# makey_makey.net
KiCad netlist of a schematic drawn in EAGLE
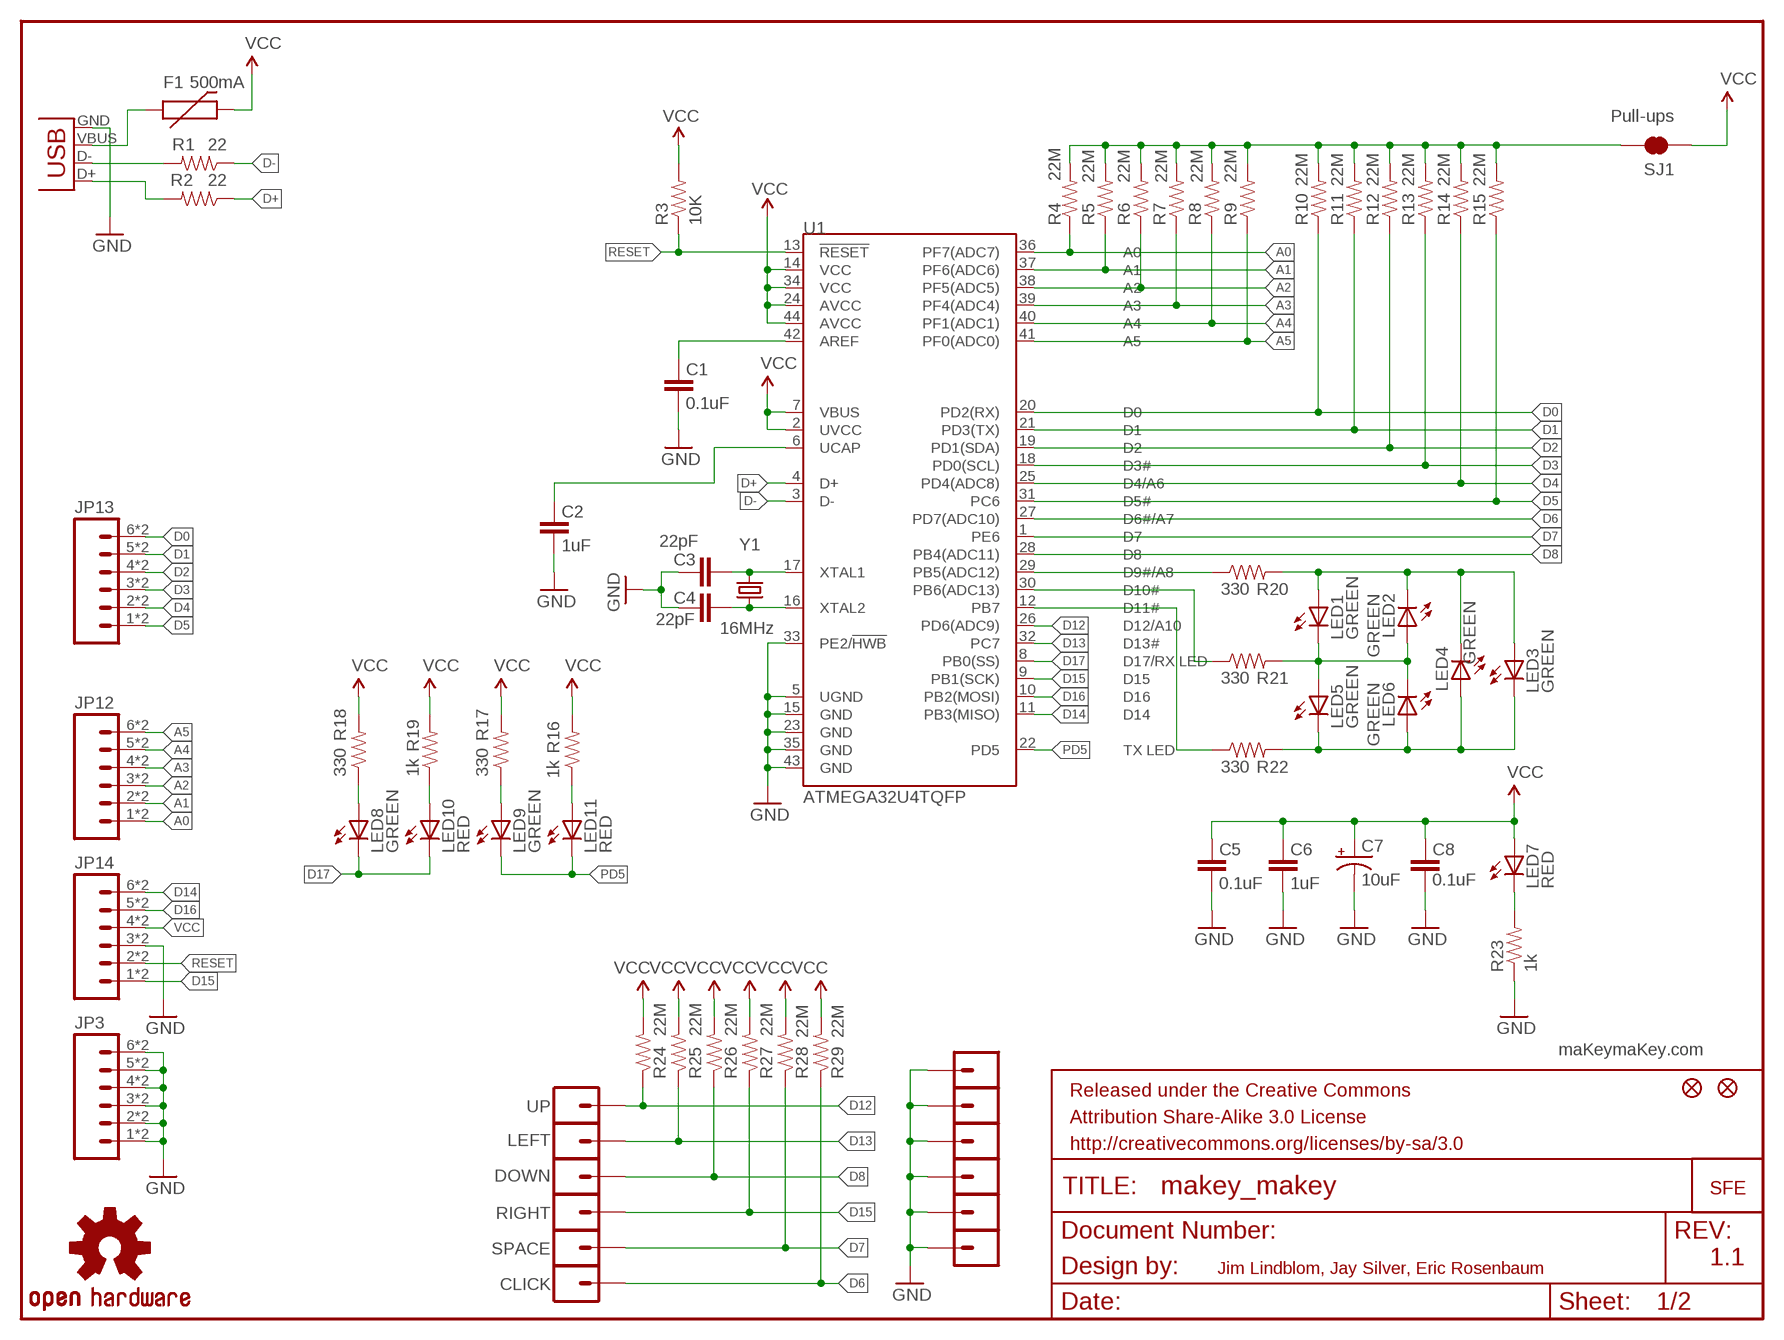
[diagram p0: schematic, sheet 1]
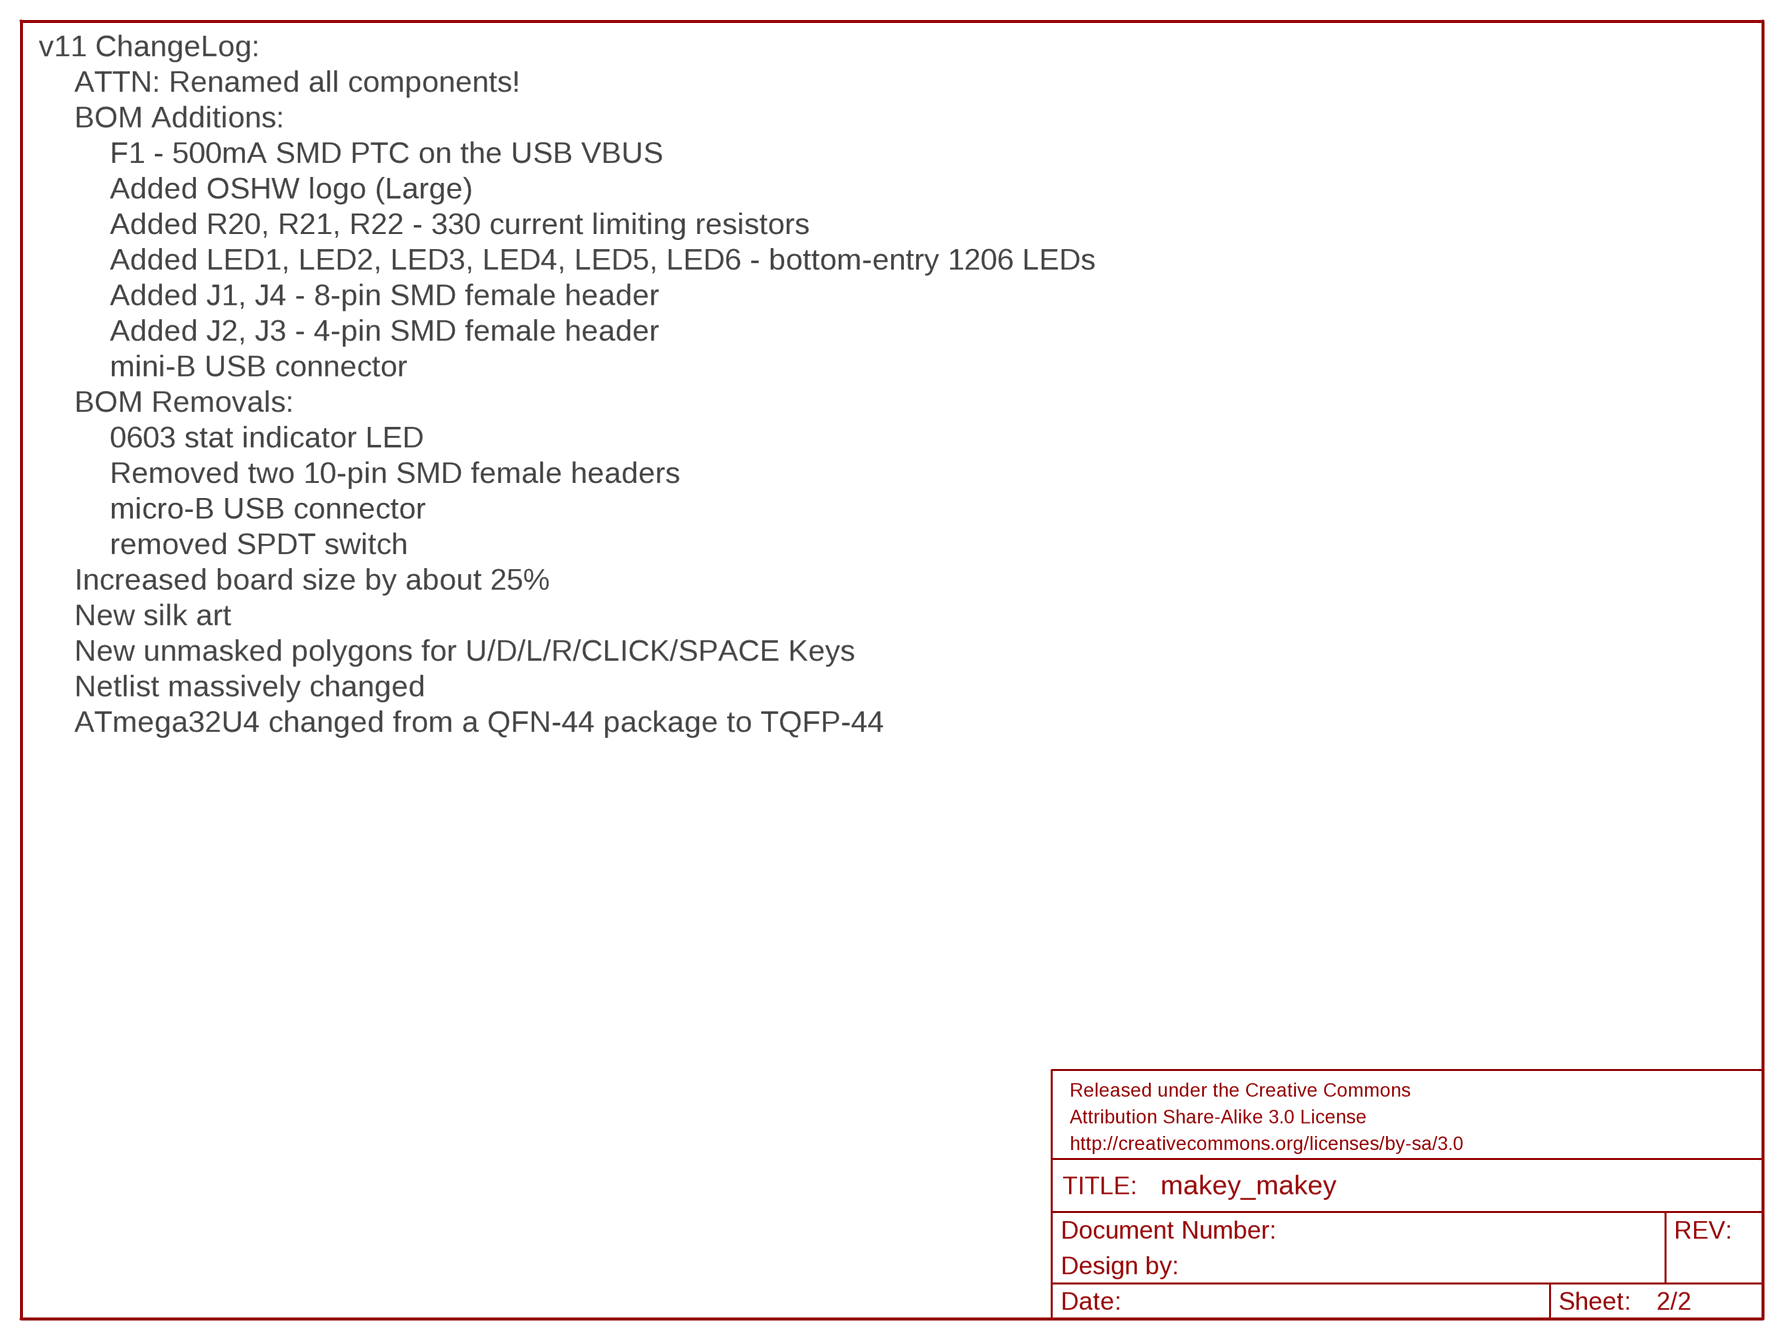
[diagram p1: schematic, sheet 2]

(export (version "E")
  (design (tool "Eeschema 10.0.6"))
  (components
    (comp (ref "C1")
      (value "0.1uF")
      (footprint "eagle-import:0402-CAP")
      (libsource (lib "eagle-import") (part "CAP0402-CAP"))
    )
    (comp (ref "C2")
      (value "1uF")
      (footprint "eagle-import:0402-CAP")
      (libsource (lib "eagle-import") (part "CAP0402-CAP"))
    )
    (comp (ref "C3")
      (value "22pF")
      (footprint "eagle-import:0402-CAP")
      (libsource (lib "eagle-import") (part "CAP0402-CAP"))
    )
    (comp (ref "C4")
      (value "22pF")
      (footprint "eagle-import:0402-CAP")
      (libsource (lib "eagle-import") (part "CAP0402-CAP"))
    )
    (comp (ref "C5")
      (value "0.1uF")
      (footprint "eagle-import:0402-CAP")
      (libsource (lib "eagle-import") (part "CAP0402-CAP"))
    )
    (comp (ref "C6")
      (value "1uF")
      (footprint "eagle-import:0402-CAP")
      (libsource (lib "eagle-import") (part "CAP0402-CAP"))
    )
    (comp (ref "C7")
      (value "10uF")
      (footprint "eagle-import:EIA3216")
      (libsource (lib "eagle-import") (part "CAP_POL1206"))
    )
    (comp (ref "C8")
      (value "0.1uF")
      (footprint "eagle-import:0402-CAP")
      (libsource (lib "eagle-import") (part "CAP0402-CAP"))
    )
    (comp (ref "CLICK")
      (value "M01ALLIGATOR-3MM")
      (footprint "eagle-import:1X01_ALLIGATOR_3MM")
      (libsource (lib "eagle-import") (part "M01ALLIGATOR-3MM"))
    )
    (comp (ref "DOWN")
      (value "M01ALLIGATOR-3MM")
      (footprint "eagle-import:1X01_ALLIGATOR_3MM")
      (libsource (lib "eagle-import") (part "M01ALLIGATOR-3MM"))
    )
    (comp (ref "F1")
      (value "500mA")
      (footprint "eagle-import:PTC-1206")
      (libsource (lib "eagle-import") (part "PTCSMD"))
    )
    (comp (ref "JP1")
      (value "FIDUCIALUFIDUCIAL")
      (footprint "eagle-import:MICRO-FIDUCIAL")
      (libsource (lib "eagle-import") (part "FIDUCIALUFIDUCIAL"))
    )
    (comp (ref "JP2")
      (value "FIDUCIALUFIDUCIAL")
      (footprint "eagle-import:MICRO-FIDUCIAL")
      (libsource (lib "eagle-import") (part "FIDUCIALUFIDUCIAL"))
    )
    (comp (ref "JP3")
      (value "M06SMD-STRAIGHT-COMBO")
      (footprint "eagle-import:1X06_SMD_STRAIGHT_COMBO")
      (libsource (lib "eagle-import") (part "M06SMD-STRAIGHT-COMBO"))
    )
    (comp (ref "JP5")
      (value "M01ALLIGATOR-3MM")
      (footprint "eagle-import:1X01_ALLIGATOR_3MM")
      (libsource (lib "eagle-import") (part "M01ALLIGATOR-3MM"))
    )
    (comp (ref "JP6")
      (value "M01ALLIGATOR-3MM")
      (footprint "eagle-import:1X01_ALLIGATOR_3MM")
      (libsource (lib "eagle-import") (part "M01ALLIGATOR-3MM"))
    )
    (comp (ref "JP7")
      (value "M01ALLIGATOR-3MM")
      (footprint "eagle-import:1X01_ALLIGATOR_3MM")
      (libsource (lib "eagle-import") (part "M01ALLIGATOR-3MM"))
    )
    (comp (ref "JP8")
      (value "M01ALLIGATOR-3MM")
      (footprint "eagle-import:1X01_ALLIGATOR_3MM")
      (libsource (lib "eagle-import") (part "M01ALLIGATOR-3MM"))
    )
    (comp (ref "JP9")
      (value "LOGO-SFENEW")
      (footprint "eagle-import:SFE-NEW-WEBLOGO")
      (libsource (lib "eagle-import") (part "LOGO-SFENEW"))
    )
    (comp (ref "JP10")
      (value "M01ALLIGATOR-3MM")
      (footprint "eagle-import:1X01_ALLIGATOR_3MM")
      (libsource (lib "eagle-import") (part "M01ALLIGATOR-3MM"))
    )
    (comp (ref "JP11")
      (value "M01ALLIGATOR-3MM")
      (footprint "eagle-import:1X01_ALLIGATOR_3MM")
      (libsource (lib "eagle-import") (part "M01ALLIGATOR-3MM"))
    )
    (comp (ref "JP12")
      (value "M06SMD-STRAIGHT-COMBO")
      (footprint "eagle-import:1X06_SMD_STRAIGHT_COMBO")
      (libsource (lib "eagle-import") (part "M06SMD-STRAIGHT-COMBO"))
    )
    (comp (ref "JP13")
      (value "M06SMD-STRAIGHT-COMBO")
      (footprint "eagle-import:1X06_SMD_STRAIGHT_COMBO")
      (libsource (lib "eagle-import") (part "M06SMD-STRAIGHT-COMBO"))
    )
    (comp (ref "JP14")
      (value "M06SMD-STRAIGHT-COMBO")
      (footprint "eagle-import:1X06_SMD_STRAIGHT_COMBO")
      (libsource (lib "eagle-import") (part "M06SMD-STRAIGHT-COMBO"))
    )
    (comp (ref "LED1")
      (value "GREEN")
      (footprint "eagle-import:LED-1206-BOTTOM")
      (libsource (lib "eagle-import") (part "LED1206-BOTTOM"))
    )
    (comp (ref "LED2")
      (value "GREEN")
      (footprint "eagle-import:LED-1206-BOTTOM")
      (libsource (lib "eagle-import") (part "LED1206-BOTTOM"))
    )
    (comp (ref "LED3")
      (value "GREEN")
      (footprint "eagle-import:LED-1206-BOTTOM")
      (libsource (lib "eagle-import") (part "LED1206-BOTTOM"))
    )
    (comp (ref "LED4")
      (value "GREEN")
      (footprint "eagle-import:LED-1206-BOTTOM")
      (libsource (lib "eagle-import") (part "LED1206-BOTTOM"))
    )
    (comp (ref "LED5")
      (value "GREEN")
      (footprint "eagle-import:LED-1206-BOTTOM")
      (libsource (lib "eagle-import") (part "LED1206-BOTTOM"))
    )
    (comp (ref "LED6")
      (value "GREEN")
      (footprint "eagle-import:LED-1206-BOTTOM")
      (libsource (lib "eagle-import") (part "LED1206-BOTTOM"))
    )
    (comp (ref "LED7")
      (value "RED")
      (footprint "eagle-import:LED-0603")
      (libsource (lib "eagle-import") (part "LED0603"))
    )
    (comp (ref "LED8")
      (value "GREEN")
      (footprint "eagle-import:LED-0603")
      (libsource (lib "eagle-import") (part "SparkFun-LED_LED0603"))
    )
    (comp (ref "LED9")
      (value "GREEN")
      (footprint "eagle-import:LED-0603")
      (libsource (lib "eagle-import") (part "SparkFun-LED_LED0603"))
    )
    (comp (ref "LED10")
      (value "RED")
      (footprint "eagle-import:LED-0603")
      (libsource (lib "eagle-import") (part "SparkFun-LED_LED0603"))
    )
    (comp (ref "LED11")
      (value "RED")
      (footprint "eagle-import:LED-0603")
      (libsource (lib "eagle-import") (part "SparkFun-LED_LED0603"))
    )
    (comp (ref "LEFT")
      (value "M01ALLIGATOR-3MM")
      (footprint "eagle-import:1X01_ALLIGATOR_3MM")
      (libsource (lib "eagle-import") (part "M01ALLIGATOR-3MM"))
    )
    (comp (ref "R1")
      (value "22")
      (footprint "eagle-import:0402-RES")
      (libsource (lib "eagle-import") (part "RESISTOR0402-RES"))
    )
    (comp (ref "R2")
      (value "22")
      (footprint "eagle-import:0402-RES")
      (libsource (lib "eagle-import") (part "RESISTOR0402-RES"))
    )
    (comp (ref "R3")
      (value "10K")
      (footprint "eagle-import:0402-RES")
      (libsource (lib "eagle-import") (part "RESISTOR0402-RES"))
    )
    (comp (ref "R4")
      (value "22M")
      (footprint "eagle-import:0402-RES")
      (libsource (lib "eagle-import") (part "RESISTOR0402-RES"))
    )
    (comp (ref "R5")
      (value "22M")
      (footprint "eagle-import:0402-RES")
      (libsource (lib "eagle-import") (part "RESISTOR0402-RES"))
    )
    (comp (ref "R6")
      (value "22M")
      (footprint "eagle-import:0402-RES")
      (libsource (lib "eagle-import") (part "RESISTOR0402-RES"))
    )
    (comp (ref "R7")
      (value "22M")
      (footprint "eagle-import:0402-RES")
      (libsource (lib "eagle-import") (part "RESISTOR0402-RES"))
    )
    (comp (ref "R8")
      (value "22M")
      (footprint "eagle-import:0402-RES")
      (libsource (lib "eagle-import") (part "RESISTOR0402-RES"))
    )
    (comp (ref "R9")
      (value "22M")
      (footprint "eagle-import:0402-RES")
      (libsource (lib "eagle-import") (part "RESISTOR0402-RES"))
    )
    (comp (ref "R10")
      (value "22M")
      (footprint "eagle-import:0402-RES")
      (libsource (lib "eagle-import") (part "RESISTOR0402-RES"))
    )
    (comp (ref "R11")
      (value "22M")
      (footprint "eagle-import:0402-RES")
      (libsource (lib "eagle-import") (part "RESISTOR0402-RES"))
    )
    (comp (ref "R12")
      (value "22M")
      (footprint "eagle-import:0402-RES")
      (libsource (lib "eagle-import") (part "RESISTOR0402-RES"))
    )
    (comp (ref "R13")
      (value "22M")
      (footprint "eagle-import:0402-RES")
      (libsource (lib "eagle-import") (part "RESISTOR0402-RES"))
    )
    (comp (ref "R14")
      (value "22M")
      (footprint "eagle-import:0402-RES")
      (libsource (lib "eagle-import") (part "RESISTOR0402-RES"))
    )
    (comp (ref "R15")
      (value "22M")
      (footprint "eagle-import:0402-RES")
      (libsource (lib "eagle-import") (part "RESISTOR0402-RES"))
    )
    (comp (ref "R16")
      (value "1k")
      (footprint "eagle-import:0402-RES")
      (libsource (lib "eagle-import") (part "SparkFun-Passives_RESISTOR0402-RES"))
    )
    (comp (ref "R17")
      (value "330")
      (footprint "eagle-import:0402-RES")
      (libsource (lib "eagle-import") (part "SparkFun-Passives_RESISTOR0402-RES"))
    )
    (comp (ref "R18")
      (value "330")
      (footprint "eagle-import:0402-RES")
      (libsource (lib "eagle-import") (part "SparkFun-Passives_RESISTOR0402-RES"))
    )
    (comp (ref "R19")
      (value "1k")
      (footprint "eagle-import:0402-RES")
      (libsource (lib "eagle-import") (part "SparkFun-Passives_RESISTOR0402-RES"))
    )
    (comp (ref "R20")
      (value "330")
      (footprint "eagle-import:0402-RES")
      (libsource (lib "eagle-import") (part "SparkFun-Passives_RESISTOR0402-RES"))
    )
    (comp (ref "R21")
      (value "330")
      (footprint "eagle-import:0402-RES")
      (libsource (lib "eagle-import") (part "SparkFun-Passives_RESISTOR0402-RES"))
    )
    (comp (ref "R22")
      (value "330")
      (footprint "eagle-import:0402-RES")
      (libsource (lib "eagle-import") (part "SparkFun-Passives_RESISTOR0402-RES"))
    )
    (comp (ref "R23")
      (value "1k")
      (footprint "eagle-import:0402-RES")
      (libsource (lib "eagle-import") (part "RESISTOR0402-RES"))
    )
    (comp (ref "R24")
      (value "22M")
      (footprint "eagle-import:0402-RES")
      (libsource (lib "eagle-import") (part "RESISTOR0402-RES"))
    )
    (comp (ref "R25")
      (value "22M")
      (footprint "eagle-import:0402-RES")
      (libsource (lib "eagle-import") (part "RESISTOR0402-RES"))
    )
    (comp (ref "R26")
      (value "22M")
      (footprint "eagle-import:0402-RES")
      (libsource (lib "eagle-import") (part "RESISTOR0402-RES"))
    )
    (comp (ref "R27")
      (value "22M")
      (footprint "eagle-import:0402-RES")
      (libsource (lib "eagle-import") (part "RESISTOR0402-RES"))
    )
    (comp (ref "R28")
      (value "22M")
      (footprint "eagle-import:0402-RES")
      (libsource (lib "eagle-import") (part "RESISTOR0402-RES"))
    )
    (comp (ref "R29")
      (value "22M")
      (footprint "eagle-import:0402-RES")
      (libsource (lib "eagle-import") (part "RESISTOR0402-RES"))
    )
    (comp (ref "RIGHT")
      (value "M01ALLIGATOR-3MM")
      (footprint "eagle-import:1X01_ALLIGATOR_3MM")
      (libsource (lib "eagle-import") (part "M01ALLIGATOR-3MM"))
    )
    (comp (ref "SJ1")
      (value "Pull-ups")
      (footprint "eagle-import:SJ_2S-TRACE")
      (libsource (lib "eagle-import") (part "SOLDERJUMPER-OLDTRACE"))
    )
    (comp (ref "SPACE")
      (value "M01ALLIGATOR-3MM")
      (footprint "eagle-import:1X01_ALLIGATOR_3MM")
      (libsource (lib "eagle-import") (part "M01ALLIGATOR-3MM"))
    )
    (comp (ref "U$1")
      (value "OSHW-LOGOM")
      (footprint "eagle-import:OSHW-LOGO-M")
      (libsource (lib "eagle-import") (part "OSHW-LOGOM"))
    )
    (comp (ref "U1")
      (value "ATMEGA32U4TQFP")
      (footprint "eagle-import:TQFP44")
      (libsource (lib "eagle-import") (part "ATMEGA32U4TQFP"))
    )
    (comp (ref "UP")
      (value "M01ALLIGATOR-3MM")
      (footprint "eagle-import:1X01_ALLIGATOR_3MM")
      (libsource (lib "eagle-import") (part "M01ALLIGATOR-3MM"))
    )
    (comp (ref "X1")
      (value "USBSMD")
      (footprint "eagle-import:USB-MINIB")
      (libsource (lib "eagle-import") (part "USBSMD"))
    )
    (comp (ref "Y1")
      (value "16MHz")
      (footprint "eagle-import:CRYSTAL-SMD-5X3")
      (libsource (lib "eagle-import") (part "CRYSTAL5X3"))
    )
  )
  (nets
    (net (code "1") (name "A0") (class "Default")
      (node (ref "JP12") (pin "1") (pinfunction "1_1") (pintype "passive"))
      (node (ref "JP12") (pin "1-2") (pinfunction "1_1-2") (pintype "passive"))
      (node (ref "R4") (pin "1") (pinfunction "1_1") (pintype "passive"))
      (node (ref "U1") (pin "36") (pinfunction "PF7(ADC7)_36") (pintype "bidirectional"))
    )
    (net (code "2") (name "A1") (class "Default")
      (node (ref "JP12") (pin "2") (pinfunction "2_2") (pintype "passive"))
      (node (ref "JP12") (pin "2-2") (pinfunction "2_2-2") (pintype "passive"))
      (node (ref "R5") (pin "1") (pinfunction "1_1") (pintype "passive"))
      (node (ref "U1") (pin "37") (pinfunction "PF6(ADC6)_37") (pintype "bidirectional"))
    )
    (net (code "3") (name "A2") (class "Default")
      (node (ref "JP12") (pin "3") (pinfunction "3_3") (pintype "passive"))
      (node (ref "JP12") (pin "3-2") (pinfunction "3_3-2") (pintype "passive"))
      (node (ref "R6") (pin "1") (pinfunction "1_1") (pintype "passive"))
      (node (ref "U1") (pin "38") (pinfunction "PF5(ADC5)_38") (pintype "bidirectional"))
    )
    (net (code "4") (name "A3") (class "Default")
      (node (ref "JP12") (pin "4") (pinfunction "4_4") (pintype "passive"))
      (node (ref "JP12") (pin "4-2") (pinfunction "4_4-2") (pintype "passive"))
      (node (ref "R7") (pin "1") (pinfunction "1_1") (pintype "passive"))
      (node (ref "U1") (pin "39") (pinfunction "PF4(ADC4)_39") (pintype "bidirectional"))
    )
    (net (code "5") (name "A4") (class "Default")
      (node (ref "JP12") (pin "5") (pinfunction "5_5") (pintype "passive"))
      (node (ref "JP12") (pin "5-2") (pinfunction "5_5-2") (pintype "passive"))
      (node (ref "R8") (pin "1") (pinfunction "1_1") (pintype "passive"))
      (node (ref "U1") (pin "40") (pinfunction "PF1(ADC1)_40") (pintype "bidirectional"))
    )
    (net (code "6") (name "A5") (class "Default")
      (node (ref "JP12") (pin "6") (pinfunction "6_6") (pintype "passive"))
      (node (ref "JP12") (pin "6-2") (pinfunction "6_6-2") (pintype "passive"))
      (node (ref "R9") (pin "1") (pinfunction "1_1") (pintype "passive"))
      (node (ref "U1") (pin "41") (pinfunction "PF0(ADC0)_41") (pintype "bidirectional"))
    )
    (net (code "7") (name "D+") (class "Default")
      (node (ref "R2") (pin "1") (pinfunction "1_1") (pintype "passive"))
      (node (ref "U1") (pin "4") (pinfunction "D+_4") (pintype "bidirectional"))
    )
    (net (code "8") (name "D-") (class "Default")
      (node (ref "R1") (pin "1") (pinfunction "1_1") (pintype "passive"))
      (node (ref "U1") (pin "3") (pinfunction "D-_3") (pintype "bidirectional"))
    )
    (net (code "9") (name "D0") (class "Default")
      (node (ref "JP13") (pin "6") (pinfunction "6_6") (pintype "passive"))
      (node (ref "JP13") (pin "6-2") (pinfunction "6_6-2") (pintype "passive"))
      (node (ref "R10") (pin "1") (pinfunction "1_1") (pintype "passive"))
      (node (ref "U1") (pin "20") (pinfunction "PD2(RX)_20") (pintype "bidirectional"))
    )
    (net (code "10") (name "D1") (class "Default")
      (node (ref "JP13") (pin "5") (pinfunction "5_5") (pintype "passive"))
      (node (ref "JP13") (pin "5-2") (pinfunction "5_5-2") (pintype "passive"))
      (node (ref "R11") (pin "1") (pinfunction "1_1") (pintype "passive"))
      (node (ref "U1") (pin "21") (pinfunction "PD3(TX)_21") (pintype "bidirectional"))
    )
    (net (code "11") (name "D2") (class "Default")
      (node (ref "JP13") (pin "4") (pinfunction "4_4") (pintype "passive"))
      (node (ref "JP13") (pin "4-2") (pinfunction "4_4-2") (pintype "passive"))
      (node (ref "R12") (pin "1") (pinfunction "1_1") (pintype "passive"))
      (node (ref "U1") (pin "19") (pinfunction "PD1(SDA)_19") (pintype "bidirectional"))
    )
    (net (code "12") (name "D3") (class "Default")
      (node (ref "JP13") (pin "3") (pinfunction "3_3") (pintype "passive"))
      (node (ref "JP13") (pin "3-2") (pinfunction "3_3-2") (pintype "passive"))
      (node (ref "R13") (pin "1") (pinfunction "1_1") (pintype "passive"))
      (node (ref "U1") (pin "18") (pinfunction "PD0(SCL)_18") (pintype "bidirectional"))
    )
    (net (code "13") (name "D4") (class "Default")
      (node (ref "JP13") (pin "2") (pinfunction "2_2") (pintype "passive"))
      (node (ref "JP13") (pin "2-2") (pinfunction "2_2-2") (pintype "passive"))
      (node (ref "R14") (pin "1") (pinfunction "1_1") (pintype "passive"))
      (node (ref "U1") (pin "25") (pinfunction "PD4(ADC8)_25") (pintype "bidirectional"))
    )
    (net (code "14") (name "D5") (class "Default")
      (node (ref "JP13") (pin "1") (pinfunction "1_1") (pintype "passive"))
      (node (ref "JP13") (pin "1-2") (pinfunction "1_1-2") (pintype "passive"))
      (node (ref "R15") (pin "1") (pinfunction "1_1") (pintype "passive"))
      (node (ref "U1") (pin "31") (pinfunction "PC6_31") (pintype "bidirectional"))
    )
    (net (code "15") (name "D6") (class "Default")
      (node (ref "CLICK") (pin "1@0") (pinfunction "1_1@0") (pintype "passive"))
      (node (ref "CLICK") (pin "1@2") (pinfunction "1_1@2") (pintype "passive"))
      (node (ref "R29") (pin "1") (pinfunction "1_1") (pintype "passive"))
      (node (ref "U1") (pin "27") (pinfunction "PD7(ADC10)_27") (pintype "bidirectional"))
    )
    (net (code "16") (name "D7") (class "Default")
      (node (ref "R28") (pin "1") (pinfunction "1_1") (pintype "passive"))
      (node (ref "SPACE") (pin "1@0") (pinfunction "1_1@0") (pintype "passive"))
      (node (ref "SPACE") (pin "1@2") (pinfunction "1_1@2") (pintype "passive"))
      (node (ref "U1") (pin "1") (pinfunction "PE6_1") (pintype "bidirectional"))
    )
    (net (code "17") (name "D8") (class "Default")
      (node (ref "DOWN") (pin "1@0") (pinfunction "1_1@0") (pintype "passive"))
      (node (ref "DOWN") (pin "1@2") (pinfunction "1_1@2") (pintype "passive"))
      (node (ref "R26") (pin "1") (pinfunction "1_1") (pintype "passive"))
      (node (ref "U1") (pin "28") (pinfunction "PB4(ADC11)_28") (pintype "bidirectional"))
    )
    (net (code "18") (name "D12") (class "Default")
      (node (ref "R24") (pin "1") (pinfunction "1_1") (pintype "passive"))
      (node (ref "U1") (pin "26") (pinfunction "PD6(ADC9)_26") (pintype "bidirectional"))
      (node (ref "UP") (pin "1@0") (pinfunction "1_1@0") (pintype "passive"))
      (node (ref "UP") (pin "1@2") (pinfunction "1_1@2") (pintype "passive"))
    )
    (net (code "19") (name "D13") (class "Default")
      (node (ref "LEFT") (pin "1@0") (pinfunction "1_1@0") (pintype "passive"))
      (node (ref "LEFT") (pin "1@2") (pinfunction "1_1@2") (pintype "passive"))
      (node (ref "R25") (pin "1") (pinfunction "1_1") (pintype "passive"))
      (node (ref "U1") (pin "32") (pinfunction "PC7_32") (pintype "bidirectional"))
    )
    (net (code "20") (name "D14") (class "Default")
      (node (ref "JP14") (pin "6") (pinfunction "6_6") (pintype "passive"))
      (node (ref "JP14") (pin "6-2") (pinfunction "6_6-2") (pintype "passive"))
      (node (ref "U1") (pin "11") (pinfunction "PB3(MISO)_11") (pintype "bidirectional"))
    )
    (net (code "21") (name "D15") (class "Default")
      (node (ref "JP14") (pin "1") (pinfunction "1_1") (pintype "passive"))
      (node (ref "JP14") (pin "1-2") (pinfunction "1_1-2") (pintype "passive"))
      (node (ref "R27") (pin "1") (pinfunction "1_1") (pintype "passive"))
      (node (ref "RIGHT") (pin "1@0") (pinfunction "1_1@0") (pintype "passive"))
      (node (ref "RIGHT") (pin "1@2") (pinfunction "1_1@2") (pintype "passive"))
      (node (ref "U1") (pin "9") (pinfunction "PB1(SCK)_9") (pintype "bidirectional"))
    )
    (net (code "22") (name "D16") (class "Default")
      (node (ref "JP14") (pin "5") (pinfunction "5_5") (pintype "passive"))
      (node (ref "JP14") (pin "5-2") (pinfunction "5_5-2") (pintype "passive"))
      (node (ref "U1") (pin "10") (pinfunction "PB2(MOSI)_10") (pintype "bidirectional"))
    )
    (net (code "23") (name "D17") (class "Default")
      (node (ref "LED10") (pin "C") (pinfunction "C_C") (pintype "passive"))
      (node (ref "LED8") (pin "C") (pinfunction "C_C") (pintype "passive"))
      (node (ref "U1") (pin "8") (pinfunction "PB0(SS)_8") (pintype "bidirectional"))
    )
    (net (code "24") (name "GND") (class "Default")
      (node (ref "C1") (pin "1") (pinfunction "1_1") (pintype "passive"))
      (node (ref "C2") (pin "1") (pinfunction "1_1") (pintype "passive"))
      (node (ref "C3") (pin "2") (pinfunction "2_2") (pintype "passive"))
      (node (ref "C4") (pin "2") (pinfunction "2_2") (pintype "passive"))
      (node (ref "C5") (pin "1") (pinfunction "1_1") (pintype "passive"))
      (node (ref "C6") (pin "1") (pinfunction "1_1") (pintype "passive"))
      (node (ref "C7") (pin "C") (pinfunction "-_C") (pintype "passive"))
      (node (ref "C8") (pin "1") (pinfunction "1_1") (pintype "passive"))
      (node (ref "JP10") (pin "1@0") (pinfunction "1_1@0") (pintype "passive"))
      (node (ref "JP10") (pin "1@2") (pinfunction "1_1@2") (pintype "passive"))
      (node (ref "JP11") (pin "1@0") (pinfunction "1_1@0") (pintype "passive"))
      (node (ref "JP11") (pin "1@2") (pinfunction "1_1@2") (pintype "passive"))
      (node (ref "JP14") (pin "3") (pinfunction "3_3") (pintype "passive"))
      (node (ref "JP14") (pin "3-2") (pinfunction "3_3-2") (pintype "passive"))
      (node (ref "JP3") (pin "1") (pinfunction "1_1") (pintype "passive"))
      (node (ref "JP3") (pin "1-2") (pinfunction "1_1-2") (pintype "passive"))
      (node (ref "JP3") (pin "2") (pinfunction "2_2") (pintype "passive"))
      (node (ref "JP3") (pin "2-2") (pinfunction "2_2-2") (pintype "passive"))
      (node (ref "JP3") (pin "3") (pinfunction "3_3") (pintype "passive"))
      (node (ref "JP3") (pin "3-2") (pinfunction "3_3-2") (pintype "passive"))
      (node (ref "JP3") (pin "4") (pinfunction "4_4") (pintype "passive"))
      (node (ref "JP3") (pin "4-2") (pinfunction "4_4-2") (pintype "passive"))
      (node (ref "JP3") (pin "5") (pinfunction "5_5") (pintype "passive"))
      (node (ref "JP3") (pin "5-2") (pinfunction "5_5-2") (pintype "passive"))
      (node (ref "JP3") (pin "6") (pinfunction "6_6") (pintype "passive"))
      (node (ref "JP3") (pin "6-2") (pinfunction "6_6-2") (pintype "passive"))
      (node (ref "JP5") (pin "1@0") (pinfunction "1_1@0") (pintype "passive"))
      (node (ref "JP5") (pin "1@2") (pinfunction "1_1@2") (pintype "passive"))
      (node (ref "JP6") (pin "1@0") (pinfunction "1_1@0") (pintype "passive"))
      (node (ref "JP6") (pin "1@2") (pinfunction "1_1@2") (pintype "passive"))
      (node (ref "JP7") (pin "1@0") (pinfunction "1_1@0") (pintype "passive"))
      (node (ref "JP7") (pin "1@2") (pinfunction "1_1@2") (pintype "passive"))
      (node (ref "JP8") (pin "1@0") (pinfunction "1_1@0") (pintype "passive"))
      (node (ref "JP8") (pin "1@2") (pinfunction "1_1@2") (pintype "passive"))
      (node (ref "R23") (pin "1") (pinfunction "1_1") (pintype "passive"))
      (node (ref "U1") (pin "15") (pinfunction "GND_15") (pintype "bidirectional"))
      (node (ref "U1") (pin "23") (pinfunction "GND_23") (pintype "bidirectional"))
      (node (ref "U1") (pin "33") (pinfunction "PE2/~{HWB}_33") (pintype "bidirectional"))
      (node (ref "U1") (pin "35") (pinfunction "GND_35") (pintype "bidirectional"))
      (node (ref "U1") (pin "43") (pinfunction "GND_43") (pintype "bidirectional"))
      (node (ref "U1") (pin "5") (pinfunction "UGND_5") (pintype "bidirectional"))
      (node (ref "X1") (pin "GND") (pinfunction "GND_GND") (pintype "bidirectional"))
    )
    (net (code "25") (name "Net-(F1-Pad1)") (class "Default")
      (node (ref "F1") (pin "1") (pinfunction "1_1") (pintype "bidirectional"))
      (node (ref "X1") (pin "VBUS") (pinfunction "VBUS_VBUS") (pintype "bidirectional"))
    )
    (net (code "26") (name "Net-(LED1-PadA)") (class "Default")
      (node (ref "LED1") (pin "A") (pinfunction "A_A") (pintype "passive"))
      (node (ref "LED2") (pin "C") (pinfunction "C_C") (pintype "passive"))
      (node (ref "LED3") (pin "A") (pinfunction "A_A") (pintype "passive"))
      (node (ref "LED4") (pin "C") (pinfunction "C_C") (pintype "passive"))
      (node (ref "R20") (pin "2") (pinfunction "2_2") (pintype "passive"))
    )
    (net (code "27") (name "Net-(LED1-PadC)") (class "Default")
      (node (ref "LED1") (pin "C") (pinfunction "C_C") (pintype "passive"))
      (node (ref "LED2") (pin "A") (pinfunction "A_A") (pintype "passive"))
      (node (ref "LED5") (pin "A") (pinfunction "A_A") (pintype "passive"))
      (node (ref "LED6") (pin "C") (pinfunction "C_C") (pintype "passive"))
      (node (ref "R21") (pin "2") (pinfunction "2_2") (pintype "passive"))
    )
    (net (code "28") (name "Net-(LED3-PadC)") (class "Default")
      (node (ref "LED3") (pin "C") (pinfunction "C_C") (pintype "passive"))
      (node (ref "LED4") (pin "A") (pinfunction "A_A") (pintype "passive"))
      (node (ref "LED5") (pin "C") (pinfunction "C_C") (pintype "passive"))
      (node (ref "LED6") (pin "A") (pinfunction "A_A") (pintype "passive"))
      (node (ref "R22") (pin "2") (pinfunction "2_2") (pintype "passive"))
    )
    (net (code "29") (name "Net-(LED7-PadC)") (class "Default")
      (node (ref "LED7") (pin "C") (pinfunction "C_C") (pintype "passive"))
      (node (ref "R23") (pin "2") (pinfunction "2_2") (pintype "passive"))
    )
    (net (code "30") (name "Net-(LED8-PadA)") (class "Default")
      (node (ref "LED8") (pin "A") (pinfunction "A_A") (pintype "passive"))
      (node (ref "R18") (pin "1") (pinfunction "1_1") (pintype "passive"))
    )
    (net (code "31") (name "Net-(LED9-PadA)") (class "Default")
      (node (ref "LED9") (pin "A") (pinfunction "A_A") (pintype "passive"))
      (node (ref "R17") (pin "1") (pinfunction "1_1") (pintype "passive"))
    )
    (net (code "32") (name "Net-(LED10-PadA)") (class "Default")
      (node (ref "LED10") (pin "A") (pinfunction "A_A") (pintype "passive"))
      (node (ref "R19") (pin "1") (pinfunction "1_1") (pintype "passive"))
    )
    (net (code "33") (name "Net-(LED11-PadA)") (class "Default")
      (node (ref "LED11") (pin "A") (pinfunction "A_A") (pintype "passive"))
      (node (ref "R16") (pin "1") (pinfunction "1_1") (pintype "passive"))
    )
    (net (code "34") (name "Net-(R1-Pad2)") (class "Default")
      (node (ref "R1") (pin "2") (pinfunction "2_2") (pintype "passive"))
      (node (ref "X1") (pin "D-") (pinfunction "D-_D-") (pintype "bidirectional"))
    )
    (net (code "35") (name "Net-(R2-Pad2)") (class "Default")
      (node (ref "R2") (pin "2") (pinfunction "2_2") (pintype "passive"))
      (node (ref "X1") (pin "D+") (pinfunction "D+_D+") (pintype "bidirectional"))
    )
    (net (code "36") (name "Net-(R10-Pad2)") (class "Default")
      (node (ref "R10") (pin "2") (pinfunction "2_2") (pintype "passive"))
      (node (ref "R11") (pin "2") (pinfunction "2_2") (pintype "passive"))
      (node (ref "R12") (pin "2") (pinfunction "2_2") (pintype "passive"))
      (node (ref "R13") (pin "2") (pinfunction "2_2") (pintype "passive"))
      (node (ref "R14") (pin "2") (pinfunction "2_2") (pintype "passive"))
      (node (ref "R15") (pin "2") (pinfunction "2_2") (pintype "passive"))
      (node (ref "R4") (pin "2") (pinfunction "2_2") (pintype "passive"))
      (node (ref "R5") (pin "2") (pinfunction "2_2") (pintype "passive"))
      (node (ref "R6") (pin "2") (pinfunction "2_2") (pintype "passive"))
      (node (ref "R7") (pin "2") (pinfunction "2_2") (pintype "passive"))
      (node (ref "R8") (pin "2") (pinfunction "2_2") (pintype "passive"))
      (node (ref "R9") (pin "2") (pinfunction "2_2") (pintype "passive"))
      (node (ref "SJ1") (pin "2") (pinfunction "2_2") (pintype "passive"))
    )
    (net (code "37") (name "Net-(U1-AREF)") (class "Default")
      (node (ref "C1") (pin "2") (pinfunction "2_2") (pintype "passive"))
      (node (ref "U1") (pin "42") (pinfunction "AREF_42") (pintype "bidirectional"))
    )
    (net (code "38") (name "Net-(U1-PB5(ADC12))") (class "Default")
      (node (ref "R20") (pin "1") (pinfunction "1_1") (pintype "passive"))
      (node (ref "U1") (pin "29") (pinfunction "PB5(ADC12)_29") (pintype "bidirectional"))
    )
    (net (code "39") (name "Net-(U1-PB6(ADC13))") (class "Default")
      (node (ref "R21") (pin "1") (pinfunction "1_1") (pintype "passive"))
      (node (ref "U1") (pin "30") (pinfunction "PB6(ADC13)_30") (pintype "bidirectional"))
    )
    (net (code "40") (name "Net-(U1-PB7)") (class "Default")
      (node (ref "R22") (pin "1") (pinfunction "1_1") (pintype "passive"))
      (node (ref "U1") (pin "12") (pinfunction "PB7_12") (pintype "bidirectional"))
    )
    (net (code "41") (name "Net-(U1-UCAP)") (class "Default")
      (node (ref "C2") (pin "2") (pinfunction "2_2") (pintype "passive"))
      (node (ref "U1") (pin "6") (pinfunction "UCAP_6") (pintype "bidirectional"))
    )
    (net (code "42") (name "Net-(U1-XTAL1)") (class "Default")
      (node (ref "C3") (pin "1") (pinfunction "1_1") (pintype "passive"))
      (node (ref "U1") (pin "17") (pinfunction "XTAL1_17") (pintype "bidirectional"))
      (node (ref "Y1") (pin "3") (pinfunction "2_3") (pintype "passive"))
    )
    (net (code "43") (name "Net-(U1-XTAL2)") (class "Default")
      (node (ref "C4") (pin "1") (pinfunction "1_1") (pintype "passive"))
      (node (ref "U1") (pin "16") (pinfunction "XTAL2_16") (pintype "bidirectional"))
      (node (ref "Y1") (pin "1") (pinfunction "1_1") (pintype "passive"))
    )
    (net (code "44") (name "PD5") (class "Default")
      (node (ref "LED11") (pin "C") (pinfunction "C_C") (pintype "passive"))
      (node (ref "LED9") (pin "C") (pinfunction "C_C") (pintype "passive"))
      (node (ref "U1") (pin "22") (pinfunction "PD5_22") (pintype "bidirectional"))
    )
    (net (code "45") (name "RESET") (class "Default")
      (node (ref "JP14") (pin "2") (pinfunction "2_2") (pintype "passive"))
      (node (ref "JP14") (pin "2-2") (pinfunction "2_2-2") (pintype "passive"))
      (node (ref "R3") (pin "1") (pinfunction "1_1") (pintype "passive"))
      (node (ref "U1") (pin "13") (pinfunction "~{RESET}_13") (pintype "bidirectional"))
    )
    (net (code "46") (name "VCC") (class "Default")
      (node (ref "C5") (pin "2") (pinfunction "2_2") (pintype "passive"))
      (node (ref "C6") (pin "2") (pinfunction "2_2") (pintype "passive"))
      (node (ref "C7") (pin "A") (pinfunction "+_A") (pintype "passive"))
      (node (ref "C8") (pin "2") (pinfunction "2_2") (pintype "passive"))
      (node (ref "F1") (pin "2") (pinfunction "2_2") (pintype "bidirectional"))
      (node (ref "JP14") (pin "4") (pinfunction "4_4") (pintype "passive"))
      (node (ref "JP14") (pin "4-2") (pinfunction "4_4-2") (pintype "passive"))
      (node (ref "LED7") (pin "A") (pinfunction "A_A") (pintype "passive"))
      (node (ref "R16") (pin "2") (pinfunction "2_2") (pintype "passive"))
      (node (ref "R17") (pin "2") (pinfunction "2_2") (pintype "passive"))
      (node (ref "R18") (pin "2") (pinfunction "2_2") (pintype "passive"))
      (node (ref "R19") (pin "2") (pinfunction "2_2") (pintype "passive"))
      (node (ref "R24") (pin "2") (pinfunction "2_2") (pintype "passive"))
      (node (ref "R25") (pin "2") (pinfunction "2_2") (pintype "passive"))
      (node (ref "R26") (pin "2") (pinfunction "2_2") (pintype "passive"))
      (node (ref "R27") (pin "2") (pinfunction "2_2") (pintype "passive"))
      (node (ref "R28") (pin "2") (pinfunction "2_2") (pintype "passive"))
      (node (ref "R29") (pin "2") (pinfunction "2_2") (pintype "passive"))
      (node (ref "R3") (pin "2") (pinfunction "2_2") (pintype "passive"))
      (node (ref "SJ1") (pin "1") (pinfunction "1_1") (pintype "passive"))
      (node (ref "U1") (pin "14") (pinfunction "VCC_14") (pintype "bidirectional"))
      (node (ref "U1") (pin "2") (pinfunction "UVCC_2") (pintype "bidirectional"))
      (node (ref "U1") (pin "24") (pinfunction "AVCC_24") (pintype "bidirectional"))
      (node (ref "U1") (pin "34") (pinfunction "VCC_34") (pintype "bidirectional"))
      (node (ref "U1") (pin "44") (pinfunction "AVCC_44") (pintype "bidirectional"))
      (node (ref "U1") (pin "7") (pinfunction "VBUS_7") (pintype "bidirectional"))
    )
  )
)
